# Cosmic.net
KiCad netlist of a schematic drawn in Altium Designer
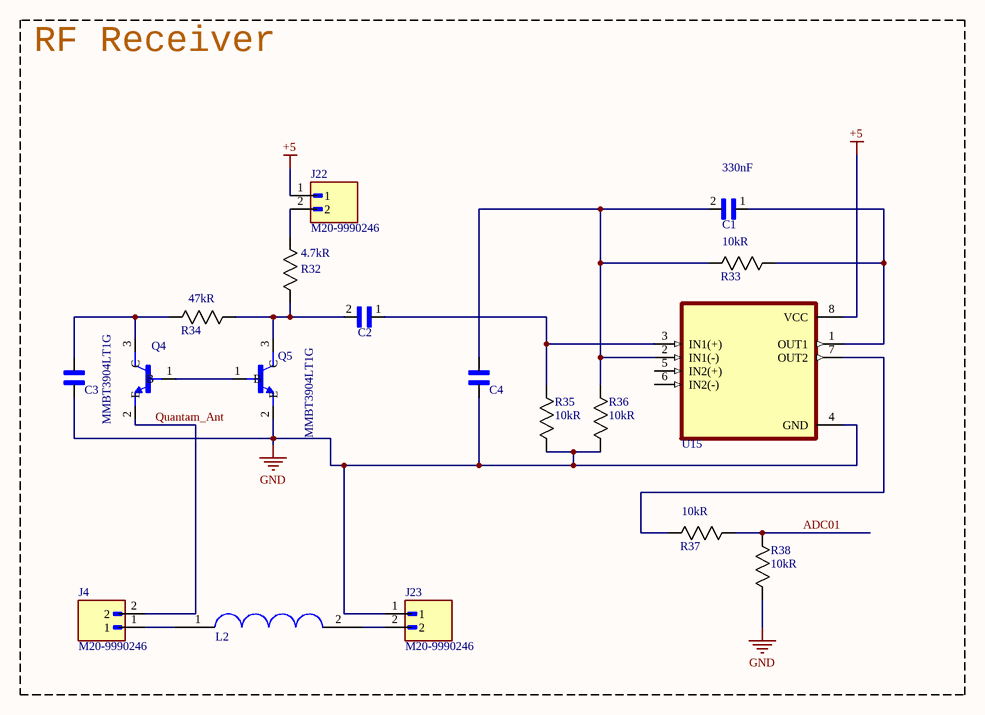
[diagram p0: Cosmic.SchDoc]

(export (version "E")
  (design (tool "Eeschema 10.0.6"))
  (components
    (comp (ref "C1")
      (value "GRM31C5C1E334GE01L")
      (footprint "CAP_1206")
      (description "Cap, 0.33Uf, 25V, 1206, C0G/Np0 Rohs Compliant: Yes ¦Murata GRM31C5C1E334GE01L")
      (fields
        (field (name "MANUFACTURER") "Murata")
        (field (name "CAPACITANCE") "330nF")
        (field (name "TOLERANCE") "2%")
      )
      (libsource (lib "Passive") (part "C334_1206"))
    )
    (comp (ref "C2")
      (value "GRM31C5C1E334GE01L")
      (footprint "CAP_1206")
      (description "Cap, 0.33Uf, 25V, 1206, C0G/Np0 Rohs Compliant: Yes ¦Murata GRM31C5C1E334GE01L")
      (fields (field (name "MANUFACTURER") "Murata") (field (name "TOLERANCE") "2%"))
      (libsource (lib "Passive") (part "C334_1206"))
    )
    (comp (ref "C3")
      (value "CL21A106KOQNNNG")
      (footprint "CAPC2012X140N")
      (description "10 ÂµF Â±10% 16V Ceramic Capacitor X5R 0805 (2012 Metric)")
      (fields (field (name "MF") "Samsung Electro-Mechanics"))
      (libsource (lib "Passive") (part "10uF16v0805"))
    )
    (comp (ref "C4")
      (value "CL21A106KOQNNNG")
      (footprint "CAPC2012X140N")
      (description "10 ÂµF Â±10% 16V Ceramic Capacitor X5R 0805 (2012 Metric)")
      (fields (field (name "MF") "Samsung Electro-Mechanics"))
      (libsource (lib "Passive") (part "10uF16v0805"))
    )
    (comp (ref "J4")
      (value "M20-9990246")
      (footprint "HARWIN_M20-9990246")
      (description "2.54mm (0.1) Pitch SIL Vertical Throughboard Pin Header, 6.1mm mating pin height, tin, 2 contacts")
      (fields (field (name "MF") "Harwin"))
      (libsource (lib "") (part "M20-9990246_1"))
    )
    (comp (ref "J22")
      (value "M20-9990246")
      (footprint "HARWIN_M20-9990246")
      (description "2.54mm (0.1) Pitch SIL Vertical Throughboard Pin Header, 6.1mm mating pin height, tin, 2 contacts")
      (fields (field (name "MF") "Harwin"))
      (libsource (lib "koncept") (part "M20-9990246"))
    )
    (comp (ref "J23")
      (value "M20-9990246")
      (footprint "HARWIN_M20-9990246")
      (description "2.54mm (0.1) Pitch SIL Vertical Throughboard Pin Header, 6.1mm mating pin height, tin, 2 contacts")
      (fields (field (name "MF") "Harwin"))
      (libsource (lib "koncept") (part "M20-9990246"))
    )
    (comp (ref "L2")
      (value "COIL_PLANNER_A")
      (footprint "COIL_PLANNER_A")
      (libsource (lib "koncept") (part "COIL_PLANNER_A"))
    )
    (comp (ref "Q4")
      (value "MMBT3904LT1G")
      (footprint "SOT95P240X111-3N")
      (fields (field (name "MF") "ON Semiconductor"))
      (libsource (lib "") (part "MMBT3904LT1G_1"))
    )
    (comp (ref "Q5")
      (value "MMBT3904LT1G")
      (footprint "SOT95P240X111-3N")
      (fields (field (name "MF") "ON Semiconductor"))
      (libsource (lib "Passive") (part "MMBT3904LT1G"))
    )
    (comp (ref "R32")
      (value "RC1206FR-074K7L")
      (footprint "STA_RMCF1206_STP-L")
      (description "SMD Chip Resistor 4.7 Kohm ½ 1% 250 Mw 1206 [3216 Metric] Thick Film General Purpose")
      (fields
        (field (name "MANUFACTURER") "Yageo")
        (field (name "TOLERANCE") "1%")
        (field (name "RESISTANCE") "4.7kR")
      )
      (libsource (lib "Passive") (part "R4K7_1206F"))
    )
    (comp (ref "R33")
      (value "RC1206FR-0710KL")
      (footprint "STA_RMCF1206_STP-L")
      (description "250Mw Thick Film Resistors 100Ppm/ 1% 10K 1206 Chip Resistor Surface Mount Rohs")
      (fields
        (field (name "MANUFACTURER") "Yageo")
        (field (name "RESISTANCE") "10kR")
        (field (name "TOLERANCE") "1%")
      )
      (libsource (lib "Passive") (part "R10K-1206"))
    )
    (comp (ref "R34")
      (value "CRGCQ1206F47K")
      (footprint "STA_RMCF1206_STP-L")
      (description "SMD Chip Resistor, 47 kOhm, ± 1%, 250 mW, 1206 [3216 Metric], Thick Film, General Purpose")
      (fields
        (field (name "MANUFACTURER") "TE Connectivity")
        (field (name "RESISTANCE") "47kR")
        (field (name "TOLERANCE") "1%")
      )
      (libsource (lib "Passive") (part "R47K1206F"))
    )
    (comp (ref "R35")
      (value "RC1206FR-0710KL")
      (footprint "STA_RMCF1206_STP-L")
      (description "250Mw Thick Film Resistors 100Ppm/ 1% 10K 1206 Chip Resistor Surface Mount Rohs")
      (fields
        (field (name "MANUFACTURER") "Yageo")
        (field (name "RESISTANCE") "10kR")
        (field (name "TOLERANCE") "1%")
      )
      (libsource (lib "Passive") (part "R10K-1206"))
    )
    (comp (ref "R36")
      (value "RC1206FR-0710KL")
      (footprint "STA_RMCF1206_STP-L")
      (description "250Mw Thick Film Resistors 100Ppm/ 1% 10K 1206 Chip Resistor Surface Mount Rohs")
      (fields
        (field (name "MANUFACTURER") "Yageo")
        (field (name "RESISTANCE") "10kR")
        (field (name "TOLERANCE") "1%")
      )
      (libsource (lib "Passive") (part "R10K-1206"))
    )
    (comp (ref "R37")
      (value "RC1206FR-0710KL")
      (footprint "STA_RMCF1206_STP-L")
      (description "250Mw Thick Film Resistors 100Ppm/ 1% 10K 1206 Chip Resistor Surface Mount Rohs")
      (fields
        (field (name "MANUFACTURER") "Yageo")
        (field (name "RESISTANCE") "10kR")
        (field (name "TOLERANCE") "1%")
      )
      (libsource (lib "Passive") (part "R10K-1206"))
    )
    (comp (ref "R38")
      (value "RC1206FR-0710KL")
      (footprint "STA_RMCF1206_STP-L")
      (description "250Mw Thick Film Resistors 100Ppm/ 1% 10K 1206 Chip Resistor Surface Mount Rohs")
      (fields
        (field (name "MANUFACTURER") "Yageo")
        (field (name "RESISTANCE") "10kR")
        (field (name "TOLERANCE") "1%")
      )
      (libsource (lib "Passive") (part "R10K-1206"))
    )
    (comp (ref "U15")
      (value "LM358MX/NOPB")
      (footprint "SOIC127P599X175-8N")
      (description "ROHS3Compliant EAR99 LM358 Tape & Reel (TR) op amp amplifier circuit 4.9mm 0.05muA 7mV 1000kHz")
      (fields (field (name "MANUFACTURER") "TI National Semiconductor"))
      (libsource (lib "koncept") (part "LM358MX/NOPB"))
    )
  )
  (nets
    (net (code "1") (name "+5") (class "Default")
      (node (ref "J22") (pin "1") (pinfunction "1_1") (pintype "passive"))
      (node (ref "U15") (pin "8") (pinfunction "VCC_8") (pintype "power_in"))
    )
    (net (code "2") (name "/ADC01") (class "Default")
      (node (ref "R37") (pin "2") (pinfunction "2_2") (pintype "passive"))
      (node (ref "R38") (pin "2") (pinfunction "2_2") (pintype "passive"))
    )
    (net (code "3") (name "/Quantam_Ant") (class "Default")
      (node (ref "J4") (pin "2") (pinfunction "2_2") (pintype "passive"))
      (node (ref "Q4") (pin "2") (pinfunction "E_2") (pintype "passive"))
    )
    (net (code "4") (name "GND") (class "Default")
      (node (ref "C3") (pin "1") (pinfunction "1_1") (pintype "passive"))
      (node (ref "C4") (pin "1") (pinfunction "1_1") (pintype "passive"))
      (node (ref "J23") (pin "1") (pinfunction "1_1") (pintype "passive"))
      (node (ref "Q5") (pin "2") (pinfunction "E_2") (pintype "passive"))
      (node (ref "R35") (pin "1") (pinfunction "1_1") (pintype "passive"))
      (node (ref "R36") (pin "1") (pinfunction "1_1") (pintype "passive"))
      (node (ref "R38") (pin "1") (pinfunction "1_1") (pintype "passive"))
      (node (ref "U15") (pin "4") (pinfunction "GND_4") (pintype "power_in"))
    )
    (net (code "5") (name "Net-(J4-Pad1)") (class "Default")
      (node (ref "J4") (pin "1") (pinfunction "1_1") (pintype "passive"))
      (node (ref "L2") (pin "1") (pinfunction "1_1") (pintype "passive"))
    )
    (net (code "6") (name "Net-(J22-Pad2)") (class "Default")
      (node (ref "J22") (pin "2") (pinfunction "2_2") (pintype "passive"))
      (node (ref "R32") (pin "2") (pinfunction "2_2") (pintype "passive"))
    )
    (net (code "7") (name "Net-(J23-Pad2)") (class "Default")
      (node (ref "J23") (pin "2") (pinfunction "2_2") (pintype "passive"))
      (node (ref "L2") (pin "2") (pinfunction "2_2") (pintype "passive"))
    )
    (net (code "8") (name "Net-(Q4-B)") (class "Default")
      (node (ref "Q4") (pin "1") (pinfunction "B_1") (pintype "passive"))
      (node (ref "Q5") (pin "1") (pinfunction "B_1") (pintype "passive"))
    )
    (net (code "9") (name "Net-(Q4-C)") (class "Default")
      (node (ref "C3") (pin "2") (pinfunction "2_2") (pintype "passive"))
      (node (ref "Q4") (pin "3") (pinfunction "C_3") (pintype "passive"))
      (node (ref "R34") (pin "1") (pinfunction "1_1") (pintype "passive"))
    )
    (net (code "10") (name "Net-(Q5-C)") (class "Default")
      (node (ref "C2") (pin "2") (pinfunction "2_2") (pintype "passive"))
      (node (ref "Q5") (pin "3") (pinfunction "C_3") (pintype "passive"))
      (node (ref "R32") (pin "1") (pinfunction "1_1") (pintype "passive"))
      (node (ref "R34") (pin "2") (pinfunction "2_2") (pintype "passive"))
    )
    (net (code "11") (name "Net-(U15-IN1(+))") (class "Default")
      (node (ref "C2") (pin "1") (pinfunction "1_1") (pintype "passive"))
      (node (ref "R35") (pin "2") (pinfunction "2_2") (pintype "passive"))
      (node (ref "U15") (pin "3") (pinfunction "IN1(+)_3") (pintype "input"))
    )
    (net (code "12") (name "Net-(U15-IN1(-))") (class "Default")
      (node (ref "C1") (pin "2") (pinfunction "2_2") (pintype "passive"))
      (node (ref "C4") (pin "2") (pinfunction "2_2") (pintype "passive"))
      (node (ref "R33") (pin "1") (pinfunction "1_1") (pintype "passive"))
      (node (ref "R36") (pin "2") (pinfunction "2_2") (pintype "passive"))
      (node (ref "U15") (pin "2") (pinfunction "IN1(-)_2") (pintype "input"))
    )
    (net (code "13") (name "Net-(U15-OUT1)") (class "Default")
      (node (ref "C1") (pin "1") (pinfunction "1_1") (pintype "passive"))
      (node (ref "R33") (pin "2") (pinfunction "2_2") (pintype "passive"))
      (node (ref "U15") (pin "1") (pinfunction "OUT1_1") (pintype "output"))
    )
    (net (code "14") (name "Net-(U15-OUT2)") (class "Default")
      (node (ref "R37") (pin "1") (pinfunction "1_1") (pintype "passive"))
      (node (ref "U15") (pin "7") (pinfunction "OUT2_7") (pintype "output"))
    )
    (net (code "15") (name "unconnected-(U15-IN2(+)-Pad5)") (class "Default")
      (node (ref "U15") (pin "5") (pinfunction "IN2(+)_5") (pintype "input"))
    )
    (net (code "16") (name "unconnected-(U15-IN2(-)-Pad6)") (class "Default")
      (node (ref "U15") (pin "6") (pinfunction "IN2(-)_6") (pintype "input"))
    )
  )
)
